# K7410tFFG900MGT.net
KiCad netlist of a schematic drawn in Altium Designer
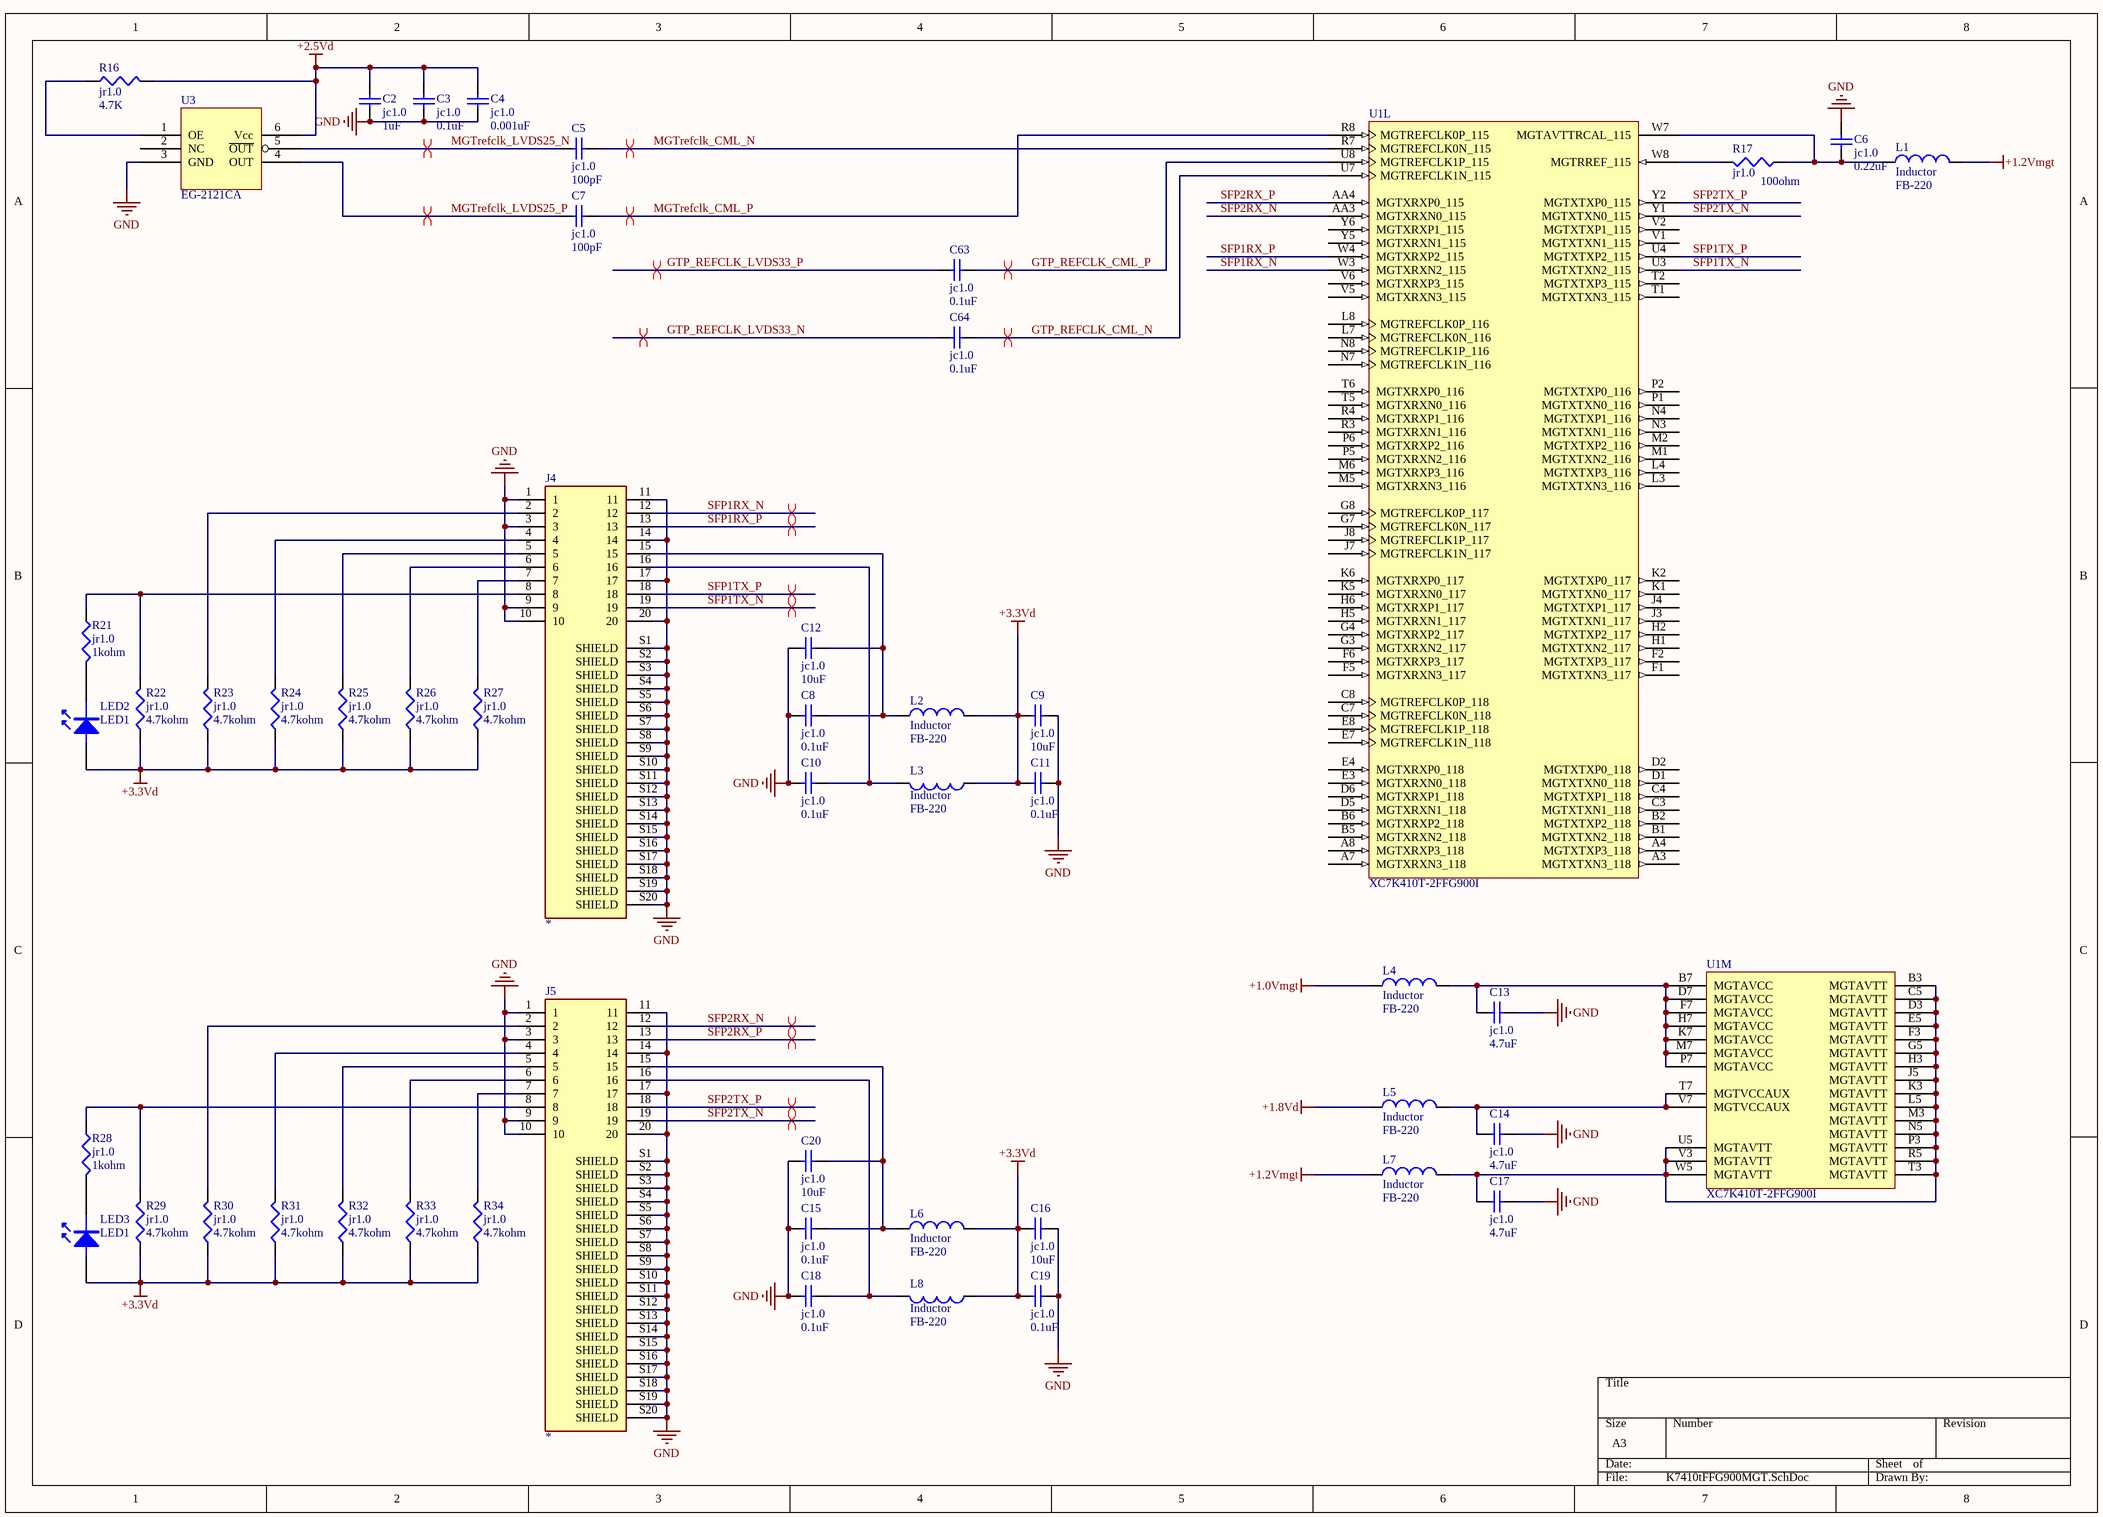
[diagram p0: K7410tFFG900MGT.SchDoc]

(export (version "E")
  (design (tool "Eeschema 10.0.6"))
  (components
    (comp (ref "C2")
      (value "jc1.0")
      (footprint "0402")
      (description "Capacitor")
      (fields (field (name "ALTIUM_VALUE") "1uF") (field (name "PUBLISHER") "Altium Limited"))
      (libsource (lib "LIB01DXP2006SchLib") (part "Cap"))
    )
    (comp (ref "C3")
      (value "jc1.0")
      (footprint "0402")
      (description "Capacitor")
      (fields (field (name "ALTIUM_VALUE") "0.1uF") (field (name "PUBLISHER") "Altium Limited"))
      (libsource (lib "LIB01DXP2006SchLib") (part "Cap"))
    )
    (comp (ref "C4")
      (value "jc1.0")
      (footprint "0402")
      (description "Capacitor")
      (fields (field (name "ALTIUM_VALUE") "0.001uF") (field (name "PUBLISHER") "Altium Limited"))
      (libsource (lib "LIB01DXP2006SchLib") (part "Cap"))
    )
    (comp (ref "C5")
      (value "jc1.0")
      (footprint "0402")
      (description "Capacitor")
      (fields (field (name "ALTIUM_VALUE") "100pF") (field (name "PUBLISHER") "Altium Limited"))
      (libsource (lib "LIB01DXP2006SchLib") (part "Cap"))
    )
    (comp (ref "C6")
      (value "jc1.0")
      (footprint "0402")
      (description "Capacitor")
      (fields (field (name "ALTIUM_VALUE") "0.22uF") (field (name "PUBLISHER") "Altium Limited"))
      (libsource (lib "LIB01DXP2006SchLib") (part "Cap"))
    )
    (comp (ref "C7")
      (value "jc1.0")
      (footprint "0402")
      (description "Capacitor")
      (fields (field (name "ALTIUM_VALUE") "100pF") (field (name "PUBLISHER") "Altium Limited"))
      (libsource (lib "LIB01DXP2006SchLib") (part "Cap"))
    )
    (comp (ref "C8")
      (value "jc1.0")
      (footprint "0805")
      (description "Capacitor")
      (fields (field (name "ALTIUM_VALUE") "0.1uF") (field (name "PUBLISHER") "Altium Limited"))
      (libsource (lib "LIB01DXP2006SchLib") (part "Cap"))
    )
    (comp (ref "C9")
      (value "jc1.0")
      (footprint "0805")
      (description "Capacitor")
      (fields (field (name "ALTIUM_VALUE") "10uF") (field (name "PUBLISHER") "Altium Limited"))
      (libsource (lib "LIB01DXP2006SchLib") (part "Cap"))
    )
    (comp (ref "C10")
      (value "jc1.0")
      (footprint "0805")
      (description "Capacitor")
      (fields (field (name "ALTIUM_VALUE") "0.1uF") (field (name "PUBLISHER") "Altium Limited"))
      (libsource (lib "LIB01DXP2006SchLib") (part "Cap"))
    )
    (comp (ref "C11")
      (value "jc1.0")
      (footprint "0805")
      (description "Capacitor")
      (fields (field (name "ALTIUM_VALUE") "0.1uF") (field (name "PUBLISHER") "Altium Limited"))
      (libsource (lib "LIB01DXP2006SchLib") (part "Cap"))
    )
    (comp (ref "C12")
      (value "jc1.0")
      (footprint "0805")
      (description "Capacitor")
      (fields (field (name "ALTIUM_VALUE") "10uF") (field (name "PUBLISHER") "Altium Limited"))
      (libsource (lib "LIB01DXP2006SchLib") (part "Cap"))
    )
    (comp (ref "C13")
      (value "jc1.0")
      (footprint "0402")
      (description "Capacitor")
      (fields (field (name "ALTIUM_VALUE") "4.7uF") (field (name "PUBLISHER") "Altium Limited"))
      (libsource (lib "LIB01DXP2006SchLib") (part "Cap"))
    )
    (comp (ref "C14")
      (value "jc1.0")
      (footprint "0402")
      (description "Capacitor")
      (fields (field (name "ALTIUM_VALUE") "4.7uF") (field (name "PUBLISHER") "Altium Limited"))
      (libsource (lib "LIB01DXP2006SchLib") (part "Cap"))
    )
    (comp (ref "C15")
      (value "jc1.0")
      (footprint "0805")
      (description "Capacitor")
      (fields (field (name "ALTIUM_VALUE") "0.1uF") (field (name "PUBLISHER") "Altium Limited"))
      (libsource (lib "LIB01DXP2006SchLib") (part "Cap"))
    )
    (comp (ref "C16")
      (value "jc1.0")
      (footprint "0805")
      (description "Capacitor")
      (fields (field (name "ALTIUM_VALUE") "10uF") (field (name "PUBLISHER") "Altium Limited"))
      (libsource (lib "LIB01DXP2006SchLib") (part "Cap"))
    )
    (comp (ref "C17")
      (value "jc1.0")
      (footprint "0402")
      (description "Capacitor")
      (fields (field (name "ALTIUM_VALUE") "4.7uF") (field (name "PUBLISHER") "Altium Limited"))
      (libsource (lib "LIB01DXP2006SchLib") (part "Cap"))
    )
    (comp (ref "C18")
      (value "jc1.0")
      (footprint "0805")
      (description "Capacitor")
      (fields (field (name "ALTIUM_VALUE") "0.1uF") (field (name "PUBLISHER") "Altium Limited"))
      (libsource (lib "LIB01DXP2006SchLib") (part "Cap"))
    )
    (comp (ref "C19")
      (value "jc1.0")
      (footprint "0805")
      (description "Capacitor")
      (fields (field (name "ALTIUM_VALUE") "0.1uF") (field (name "PUBLISHER") "Altium Limited"))
      (libsource (lib "LIB01DXP2006SchLib") (part "Cap"))
    )
    (comp (ref "C20")
      (value "jc1.0")
      (footprint "0805")
      (description "Capacitor")
      (fields (field (name "ALTIUM_VALUE") "10uF") (field (name "PUBLISHER") "Altium Limited"))
      (libsource (lib "LIB01DXP2006SchLib") (part "Cap"))
    )
    (comp (ref "C63")
      (value "jc1.0")
      (footprint "0402")
      (description "Capacitor")
      (fields (field (name "ALTIUM_VALUE") "0.1uF") (field (name "PUBLISHER") "Altium Limited"))
      (libsource (lib "LIB01DXP2006SchLib") (part "Cap"))
    )
    (comp (ref "C64")
      (value "jc1.0")
      (footprint "0402")
      (description "Capacitor")
      (fields (field (name "ALTIUM_VALUE") "0.1uF") (field (name "PUBLISHER") "Altium Limited"))
      (libsource (lib "LIB01DXP2006SchLib") (part "Cap"))
    )
    (comp (ref "J4")
      (value "2227023-1")
      (footprint "TE_2227023-1")
      (description "Connector Accessories 1 Port SFP Cage Press Fit Right Angle Through Hole Nickel Tray")
      (fields (field (name "MF") "TE Connectivity") (field (name "COMMENT_1") "*"))
      (libsource (lib "2227023-1") (part "2227023-1"))
    )
    (comp (ref "J5")
      (value "2227023-1")
      (footprint "TE_2227023-1")
      (description "Connector Accessories 1 Port SFP Cage Press Fit Right Angle Through Hole Nickel Tray")
      (fields (field (name "MF") "TE Connectivity") (field (name "COMMENT_1") "*"))
      (libsource (lib "2227023-1") (part "2227023-1"))
    )
    (comp (ref "L1")
      (value "Inductor")
      (footprint "0603")
      (fields (field (name "ALTIUM_VALUE") "FB-220") (field (name "PUBLISHER") "Altium Limited"))
      (libsource (lib "LIB01DXP2006SchLib") (part "Inductor"))
    )
    (comp (ref "L2")
      (value "Inductor")
      (footprint "1210")
      (fields (field (name "ALTIUM_VALUE") "FB-220") (field (name "PUBLISHER") "Altium Limited"))
      (libsource (lib "LIB01DXP2006SchLib") (part "Inductor"))
    )
    (comp (ref "L3")
      (value "Inductor")
      (footprint "1210")
      (fields (field (name "ALTIUM_VALUE") "FB-220") (field (name "PUBLISHER") "Altium Limited"))
      (libsource (lib "LIB01DXP2006SchLib") (part "Inductor"))
    )
    (comp (ref "L4")
      (value "Inductor")
      (footprint "1210")
      (fields (field (name "ALTIUM_VALUE") "FB-220") (field (name "PUBLISHER") "Altium Limited"))
      (libsource (lib "LIB01DXP2006SchLib") (part "Inductor"))
    )
    (comp (ref "L5")
      (value "Inductor")
      (footprint "1210")
      (fields (field (name "ALTIUM_VALUE") "FB-220") (field (name "PUBLISHER") "Altium Limited"))
      (libsource (lib "LIB01DXP2006SchLib") (part "Inductor"))
    )
    (comp (ref "L6")
      (value "Inductor")
      (footprint "1210")
      (fields (field (name "ALTIUM_VALUE") "FB-220") (field (name "PUBLISHER") "Altium Limited"))
      (libsource (lib "LIB01DXP2006SchLib") (part "Inductor"))
    )
    (comp (ref "L7")
      (value "Inductor")
      (footprint "1210")
      (fields (field (name "ALTIUM_VALUE") "FB-220") (field (name "PUBLISHER") "Altium Limited"))
      (libsource (lib "LIB01DXP2006SchLib") (part "Inductor"))
    )
    (comp (ref "L8")
      (value "Inductor")
      (footprint "1210")
      (fields (field (name "ALTIUM_VALUE") "FB-220") (field (name "PUBLISHER") "Altium Limited"))
      (libsource (lib "LIB01DXP2006SchLib") (part "Inductor"))
    )
    (comp (ref "LED2") (value "LED1") (footprint "LED1") (libsource (lib "LIB01DXP2006SchLib") (part "LED1")))
    (comp (ref "LED3") (value "LED1") (footprint "LED1") (libsource (lib "LIB01DXP2006SchLib") (part "LED1")))
    (comp (ref "R16")
      (value "jr1.0")
      (footprint "0402")
      (description "Resistor")
      (fields (field (name "ALTIUM_VALUE") "4.7K") (field (name "PUBLISHER") "Altium Limited"))
      (libsource (lib "LIB01DXP2006SchLib") (part "Res"))
    )
    (comp (ref "R17")
      (value "jr1.0")
      (footprint "0402")
      (description "Resistor")
      (fields (field (name "ALTIUM_VALUE") "100ohm") (field (name "PUBLISHER") "Altium Limited"))
      (libsource (lib "LIB01DXP2006SchLib") (part "Res"))
    )
    (comp (ref "R21")
      (value "jr1.0")
      (footprint "0402")
      (description "Resistor")
      (fields (field (name "ALTIUM_VALUE") "1kohm") (field (name "PUBLISHER") "Altium Limited"))
      (libsource (lib "LIB01DXP2006SchLib") (part "Res"))
    )
    (comp (ref "R22")
      (value "jr1.0")
      (footprint "0402")
      (description "Resistor")
      (fields (field (name "ALTIUM_VALUE") "4.7kohm") (field (name "PUBLISHER") "Altium Limited"))
      (libsource (lib "LIB01DXP2006SchLib") (part "Res"))
    )
    (comp (ref "R23")
      (value "jr1.0")
      (footprint "0402")
      (description "Resistor")
      (fields (field (name "ALTIUM_VALUE") "4.7kohm") (field (name "PUBLISHER") "Altium Limited"))
      (libsource (lib "LIB01DXP2006SchLib") (part "Res"))
    )
    (comp (ref "R24")
      (value "jr1.0")
      (footprint "0402")
      (description "Resistor")
      (fields (field (name "ALTIUM_VALUE") "4.7kohm") (field (name "PUBLISHER") "Altium Limited"))
      (libsource (lib "LIB01DXP2006SchLib") (part "Res"))
    )
    (comp (ref "R25")
      (value "jr1.0")
      (footprint "0402")
      (description "Resistor")
      (fields (field (name "ALTIUM_VALUE") "4.7kohm") (field (name "PUBLISHER") "Altium Limited"))
      (libsource (lib "LIB01DXP2006SchLib") (part "Res"))
    )
    (comp (ref "R26")
      (value "jr1.0")
      (footprint "0402")
      (description "Resistor")
      (fields (field (name "ALTIUM_VALUE") "4.7kohm") (field (name "PUBLISHER") "Altium Limited"))
      (libsource (lib "LIB01DXP2006SchLib") (part "Res"))
    )
    (comp (ref "R27")
      (value "jr1.0")
      (footprint "0402")
      (description "Resistor")
      (fields (field (name "ALTIUM_VALUE") "4.7kohm") (field (name "PUBLISHER") "Altium Limited"))
      (libsource (lib "LIB01DXP2006SchLib") (part "Res"))
    )
    (comp (ref "R28")
      (value "jr1.0")
      (footprint "0402")
      (description "Resistor")
      (fields (field (name "ALTIUM_VALUE") "1kohm") (field (name "PUBLISHER") "Altium Limited"))
      (libsource (lib "LIB01DXP2006SchLib") (part "Res"))
    )
    (comp (ref "R29")
      (value "jr1.0")
      (footprint "0402")
      (description "Resistor")
      (fields (field (name "ALTIUM_VALUE") "4.7kohm") (field (name "PUBLISHER") "Altium Limited"))
      (libsource (lib "LIB01DXP2006SchLib") (part "Res"))
    )
    (comp (ref "R30")
      (value "jr1.0")
      (footprint "0402")
      (description "Resistor")
      (fields (field (name "ALTIUM_VALUE") "4.7kohm") (field (name "PUBLISHER") "Altium Limited"))
      (libsource (lib "LIB01DXP2006SchLib") (part "Res"))
    )
    (comp (ref "R31")
      (value "jr1.0")
      (footprint "0402")
      (description "Resistor")
      (fields (field (name "ALTIUM_VALUE") "4.7kohm") (field (name "PUBLISHER") "Altium Limited"))
      (libsource (lib "LIB01DXP2006SchLib") (part "Res"))
    )
    (comp (ref "R32")
      (value "jr1.0")
      (footprint "0402")
      (description "Resistor")
      (fields (field (name "ALTIUM_VALUE") "4.7kohm") (field (name "PUBLISHER") "Altium Limited"))
      (libsource (lib "LIB01DXP2006SchLib") (part "Res"))
    )
    (comp (ref "R33")
      (value "jr1.0")
      (footprint "0402")
      (description "Resistor")
      (fields (field (name "ALTIUM_VALUE") "4.7kohm") (field (name "PUBLISHER") "Altium Limited"))
      (libsource (lib "LIB01DXP2006SchLib") (part "Res"))
    )
    (comp (ref "R34")
      (value "jr1.0")
      (footprint "0402")
      (description "Resistor")
      (fields (field (name "ALTIUM_VALUE") "4.7kohm") (field (name "PUBLISHER") "Altium Limited"))
      (libsource (lib "LIB01DXP2006SchLib") (part "Res"))
    )
    (comp (ref "U1")
      (value "XC7K410T-2FFG900I")
      (footprint "FFG900")
      (description "Kintex-7 FPGA, 500 User I/Os, 16 GTX, 900-Ball BGA, Speed Grade 2, Industrial Grade, Pb-Free")
      (fields (field (name "GENERIC PART NUMBER") "XC7K410T") (field (name "MANUFACTURER") "Xilinx"))
      (libsource (lib "Xilinx Kintex-7") (part "XC7K410T-2FFG900I"))
    )
    (comp (ref "U3")
      (value "EG-2121CA")
      (footprint "DFN3")
      (libsource (lib "LIB01DXP2006SchLib") (part "EG-2121CA"))
    )
  )
  (nets
    (net (code "1") (name "+1.0Vmgt") (class "Default")
      (node (ref "L4") (pin "1") (pinfunction "1_1") (pintype "passive"))
    )
    (net (code "2") (name "+1.2Vmgt") (class "Default")
      (node (ref "L1") (pin "2") (pinfunction "2_2") (pintype "passive"))
      (node (ref "L7") (pin "1") (pinfunction "1_1") (pintype "passive"))
    )
    (net (code "3") (name "+1.8Vd") (class "Default")
      (node (ref "L5") (pin "1") (pinfunction "1_1") (pintype "passive"))
    )
    (net (code "4") (name "+2.5Vd") (class "Default")
      (node (ref "C2") (pin "2") (pinfunction "2_2") (pintype "passive"))
      (node (ref "C3") (pin "2") (pinfunction "2_2") (pintype "passive"))
      (node (ref "C4") (pin "2") (pinfunction "2_2") (pintype "passive"))
      (node (ref "R16") (pin "2") (pinfunction "2_2") (pintype "passive"))
      (node (ref "U3") (pin "6") (pinfunction "Vcc_6") (pintype "passive"))
    )
    (net (code "5") (name "+3.3Vd") (class "Default")
      (node (ref "C11") (pin "2") (pinfunction "2_2") (pintype "passive"))
      (node (ref "C16") (pin "2") (pinfunction "2_2") (pintype "passive"))
      (node (ref "C19") (pin "2") (pinfunction "2_2") (pintype "passive"))
      (node (ref "C9") (pin "2") (pinfunction "2_2") (pintype "passive"))
      (node (ref "L2") (pin "2") (pinfunction "2_2") (pintype "passive"))
      (node (ref "L3") (pin "1") (pinfunction "1_1") (pintype "passive"))
      (node (ref "L6") (pin "2") (pinfunction "2_2") (pintype "passive"))
      (node (ref "L8") (pin "1") (pinfunction "1_1") (pintype "passive"))
      (node (ref "LED2") (pin "1") (pinfunction "1_1") (pintype "passive"))
      (node (ref "LED3") (pin "1") (pinfunction "1_1") (pintype "passive"))
      (node (ref "R22") (pin "1") (pinfunction "1_1") (pintype "passive"))
      (node (ref "R23") (pin "1") (pinfunction "1_1") (pintype "passive"))
      (node (ref "R24") (pin "1") (pinfunction "1_1") (pintype "passive"))
      (node (ref "R25") (pin "1") (pinfunction "1_1") (pintype "passive"))
      (node (ref "R26") (pin "1") (pinfunction "1_1") (pintype "passive"))
      (node (ref "R27") (pin "1") (pinfunction "1_1") (pintype "passive"))
      (node (ref "R29") (pin "1") (pinfunction "1_1") (pintype "passive"))
      (node (ref "R30") (pin "1") (pinfunction "1_1") (pintype "passive"))
      (node (ref "R31") (pin "1") (pinfunction "1_1") (pintype "passive"))
      (node (ref "R32") (pin "1") (pinfunction "1_1") (pintype "passive"))
      (node (ref "R33") (pin "1") (pinfunction "1_1") (pintype "passive"))
      (node (ref "R34") (pin "1") (pinfunction "1_1") (pintype "passive"))
    )
    (net (code "6") (name "/GTP_REFCLK_CML_N") (class "Default")
      (node (ref "C64") (pin "2") (pinfunction "2_2") (pintype "passive"))
      (node (ref "U1") (pin "U7") (pinfunction "MGTREFCLK1N_115_U7") (pintype "input"))
    )
    (net (code "7") (name "/GTP_REFCLK_CML_P") (class "Default")
      (node (ref "C63") (pin "2") (pinfunction "2_2") (pintype "passive"))
      (node (ref "U1") (pin "U8") (pinfunction "MGTREFCLK1P_115_U8") (pintype "input"))
    )
    (net (code "8") (name "/GTP_REFCLK_LVDS33_N") (class "Default")
      (node (ref "C64") (pin "1") (pinfunction "1_1") (pintype "passive"))
    )
    (net (code "9") (name "/GTP_REFCLK_LVDS33_P") (class "Default")
      (node (ref "C63") (pin "1") (pinfunction "1_1") (pintype "passive"))
    )
    (net (code "10") (name "/MGTrefclk_CML_N") (class "Default")
      (node (ref "C5") (pin "2") (pinfunction "2_2") (pintype "passive"))
      (node (ref "U1") (pin "R7") (pinfunction "MGTREFCLK0N_115_R7") (pintype "input"))
    )
    (net (code "11") (name "/MGTrefclk_CML_P") (class "Default")
      (node (ref "C7") (pin "2") (pinfunction "2_2") (pintype "passive"))
      (node (ref "U1") (pin "R8") (pinfunction "MGTREFCLK0P_115_R8") (pintype "input"))
    )
    (net (code "12") (name "/MGTrefclk_LVDS25_N") (class "Default")
      (node (ref "C5") (pin "1") (pinfunction "1_1") (pintype "passive"))
      (node (ref "U3") (pin "5") (pinfunction "~{OUT}_5") (pintype "passive"))
    )
    (net (code "13") (name "/MGTrefclk_LVDS25_P") (class "Default")
      (node (ref "C7") (pin "1") (pinfunction "1_1") (pintype "passive"))
      (node (ref "U3") (pin "4") (pinfunction "OUT_4") (pintype "passive"))
    )
    (net (code "14") (name "/SFP1RX_N") (class "Default")
      (node (ref "J4") (pin "12") (pinfunction "12_12") (pintype "passive"))
      (node (ref "U1") (pin "W3") (pinfunction "MGTXRXN2_115_W3") (pintype "input"))
    )
    (net (code "15") (name "/SFP1RX_P") (class "Default")
      (node (ref "J4") (pin "13") (pinfunction "13_13") (pintype "passive"))
      (node (ref "U1") (pin "W4") (pinfunction "MGTXRXP2_115_W4") (pintype "input"))
    )
    (net (code "16") (name "/SFP1TX_N") (class "Default")
      (node (ref "J4") (pin "19") (pinfunction "19_19") (pintype "passive"))
      (node (ref "U1") (pin "U3") (pinfunction "MGTXTXN2_115_U3") (pintype "output"))
    )
    (net (code "17") (name "/SFP1TX_P") (class "Default")
      (node (ref "J4") (pin "18") (pinfunction "18_18") (pintype "passive"))
      (node (ref "U1") (pin "U4") (pinfunction "MGTXTXP2_115_U4") (pintype "output"))
    )
    (net (code "18") (name "/SFP2RX_N") (class "Default")
      (node (ref "J5") (pin "12") (pinfunction "12_12") (pintype "passive"))
      (node (ref "U1") (pin "AA3") (pinfunction "MGTXRXN0_115_AA3") (pintype "input"))
    )
    (net (code "19") (name "/SFP2RX_P") (class "Default")
      (node (ref "J5") (pin "13") (pinfunction "13_13") (pintype "passive"))
      (node (ref "U1") (pin "AA4") (pinfunction "MGTXRXP0_115_AA4") (pintype "input"))
    )
    (net (code "20") (name "/SFP2TX_N") (class "Default")
      (node (ref "J5") (pin "19") (pinfunction "19_19") (pintype "passive"))
      (node (ref "U1") (pin "Y1") (pinfunction "MGTXTXN0_115_Y1") (pintype "output"))
    )
    (net (code "21") (name "/SFP2TX_P") (class "Default")
      (node (ref "J5") (pin "18") (pinfunction "18_18") (pintype "passive"))
      (node (ref "U1") (pin "Y2") (pinfunction "MGTXTXP0_115_Y2") (pintype "output"))
    )
    (net (code "22") (name "GND") (class "Default")
      (node (ref "C10") (pin "1") (pinfunction "1_1") (pintype "passive"))
      (node (ref "C11") (pin "1") (pinfunction "1_1") (pintype "passive"))
      (node (ref "C12") (pin "1") (pinfunction "1_1") (pintype "passive"))
      (node (ref "C13") (pin "1") (pinfunction "1_1") (pintype "passive"))
      (node (ref "C14") (pin "1") (pinfunction "1_1") (pintype "passive"))
      (node (ref "C15") (pin "1") (pinfunction "1_1") (pintype "passive"))
      (node (ref "C16") (pin "1") (pinfunction "1_1") (pintype "passive"))
      (node (ref "C17") (pin "1") (pinfunction "1_1") (pintype "passive"))
      (node (ref "C18") (pin "1") (pinfunction "1_1") (pintype "passive"))
      (node (ref "C19") (pin "1") (pinfunction "1_1") (pintype "passive"))
      (node (ref "C2") (pin "1") (pinfunction "1_1") (pintype "passive"))
      (node (ref "C20") (pin "1") (pinfunction "1_1") (pintype "passive"))
      (node (ref "C3") (pin "1") (pinfunction "1_1") (pintype "passive"))
      (node (ref "C4") (pin "1") (pinfunction "1_1") (pintype "passive"))
      (node (ref "C6") (pin "1") (pinfunction "1_1") (pintype "passive"))
      (node (ref "C8") (pin "1") (pinfunction "1_1") (pintype "passive"))
      (node (ref "C9") (pin "1") (pinfunction "1_1") (pintype "passive"))
      (node (ref "J4") (pin "1") (pinfunction "1_1") (pintype "passive"))
      (node (ref "J4") (pin "10") (pinfunction "10_10") (pintype "passive"))
      (node (ref "J4") (pin "11") (pinfunction "11_11") (pintype "passive"))
      (node (ref "J4") (pin "14") (pinfunction "14_14") (pintype "passive"))
      (node (ref "J4") (pin "17") (pinfunction "17_17") (pintype "passive"))
      (node (ref "J4") (pin "20") (pinfunction "20_20") (pintype "passive"))
      (node (ref "J4") (pin "3") (pinfunction "3_3") (pintype "passive"))
      (node (ref "J4") (pin "9") (pinfunction "9_9") (pintype "passive"))
      (node (ref "J4") (pin "S1") (pinfunction "SHIELD_S1") (pintype "passive"))
      (node (ref "J4") (pin "S10") (pinfunction "SHIELD_S10") (pintype "passive"))
      (node (ref "J4") (pin "S11") (pinfunction "SHIELD_S11") (pintype "passive"))
      (node (ref "J4") (pin "S12") (pinfunction "SHIELD_S12") (pintype "passive"))
      (node (ref "J4") (pin "S13") (pinfunction "SHIELD_S13") (pintype "passive"))
      (node (ref "J4") (pin "S14") (pinfunction "SHIELD_S14") (pintype "passive"))
      (node (ref "J4") (pin "S15") (pinfunction "SHIELD_S15") (pintype "passive"))
      (node (ref "J4") (pin "S16") (pinfunction "SHIELD_S16") (pintype "passive"))
      (node (ref "J4") (pin "S17") (pinfunction "SHIELD_S17") (pintype "passive"))
      (node (ref "J4") (pin "S18") (pinfunction "SHIELD_S18") (pintype "passive"))
      (node (ref "J4") (pin "S19") (pinfunction "SHIELD_S19") (pintype "passive"))
      (node (ref "J4") (pin "S2") (pinfunction "SHIELD_S2") (pintype "passive"))
      (node (ref "J4") (pin "S20") (pinfunction "SHIELD_S20") (pintype "passive"))
      (node (ref "J4") (pin "S3") (pinfunction "SHIELD_S3") (pintype "passive"))
      (node (ref "J4") (pin "S4") (pinfunction "SHIELD_S4") (pintype "passive"))
      (node (ref "J4") (pin "S5") (pinfunction "SHIELD_S5") (pintype "passive"))
      (node (ref "J4") (pin "S6") (pinfunction "SHIELD_S6") (pintype "passive"))
      (node (ref "J4") (pin "S7") (pinfunction "SHIELD_S7") (pintype "passive"))
      (node (ref "J4") (pin "S8") (pinfunction "SHIELD_S8") (pintype "passive"))
      (node (ref "J4") (pin "S9") (pinfunction "SHIELD_S9") (pintype "passive"))
      (node (ref "J5") (pin "1") (pinfunction "1_1") (pintype "passive"))
      (node (ref "J5") (pin "10") (pinfunction "10_10") (pintype "passive"))
      (node (ref "J5") (pin "11") (pinfunction "11_11") (pintype "passive"))
      (node (ref "J5") (pin "14") (pinfunction "14_14") (pintype "passive"))
      (node (ref "J5") (pin "17") (pinfunction "17_17") (pintype "passive"))
      (node (ref "J5") (pin "20") (pinfunction "20_20") (pintype "passive"))
      (node (ref "J5") (pin "3") (pinfunction "3_3") (pintype "passive"))
      (node (ref "J5") (pin "9") (pinfunction "9_9") (pintype "passive"))
      (node (ref "J5") (pin "S1") (pinfunction "SHIELD_S1") (pintype "passive"))
      (node (ref "J5") (pin "S10") (pinfunction "SHIELD_S10") (pintype "passive"))
      (node (ref "J5") (pin "S11") (pinfunction "SHIELD_S11") (pintype "passive"))
      (node (ref "J5") (pin "S12") (pinfunction "SHIELD_S12") (pintype "passive"))
      (node (ref "J5") (pin "S13") (pinfunction "SHIELD_S13") (pintype "passive"))
      (node (ref "J5") (pin "S14") (pinfunction "SHIELD_S14") (pintype "passive"))
      (node (ref "J5") (pin "S15") (pinfunction "SHIELD_S15") (pintype "passive"))
      (node (ref "J5") (pin "S16") (pinfunction "SHIELD_S16") (pintype "passive"))
      (node (ref "J5") (pin "S17") (pinfunction "SHIELD_S17") (pintype "passive"))
      (node (ref "J5") (pin "S18") (pinfunction "SHIELD_S18") (pintype "passive"))
      (node (ref "J5") (pin "S19") (pinfunction "SHIELD_S19") (pintype "passive"))
      (node (ref "J5") (pin "S2") (pinfunction "SHIELD_S2") (pintype "passive"))
      (node (ref "J5") (pin "S20") (pinfunction "SHIELD_S20") (pintype "passive"))
      (node (ref "J5") (pin "S3") (pinfunction "SHIELD_S3") (pintype "passive"))
      (node (ref "J5") (pin "S4") (pinfunction "SHIELD_S4") (pintype "passive"))
      (node (ref "J5") (pin "S5") (pinfunction "SHIELD_S5") (pintype "passive"))
      (node (ref "J5") (pin "S6") (pinfunction "SHIELD_S6") (pintype "passive"))
      (node (ref "J5") (pin "S7") (pinfunction "SHIELD_S7") (pintype "passive"))
      (node (ref "J5") (pin "S8") (pinfunction "SHIELD_S8") (pintype "passive"))
      (node (ref "J5") (pin "S9") (pinfunction "SHIELD_S9") (pintype "passive"))
      (node (ref "U3") (pin "3") (pinfunction "GND_3") (pintype "passive"))
    )
    (net (code "23") (name "Net-(C10-Pad2)") (class "Default")
      (node (ref "C10") (pin "2") (pinfunction "2_2") (pintype "passive"))
      (node (ref "J4") (pin "16") (pinfunction "16_16") (pintype "passive"))
      (node (ref "L3") (pin "2") (pinfunction "2_2") (pintype "passive"))
    )
    (net (code "24") (name "Net-(C12-Pad2)") (class "Default")
      (node (ref "C12") (pin "2") (pinfunction "2_2") (pintype "passive"))
      (node (ref "C8") (pin "2") (pinfunction "2_2") (pintype "passive"))
      (node (ref "J4") (pin "15") (pinfunction "15_15") (pintype "passive"))
      (node (ref "L2") (pin "1") (pinfunction "1_1") (pintype "passive"))
    )
    (net (code "25") (name "Net-(C13-Pad2)") (class "Default")
      (node (ref "C13") (pin "2") (pinfunction "2_2") (pintype "passive"))
      (node (ref "L4") (pin "2") (pinfunction "2_2") (pintype "passive"))
      (node (ref "U1") (pin "B7") (pinfunction "MGTAVCC_B7") (pintype "power_in"))
      (node (ref "U1") (pin "D7") (pinfunction "MGTAVCC_D7") (pintype "power_in"))
      (node (ref "U1") (pin "F7") (pinfunction "MGTAVCC_F7") (pintype "power_in"))
      (node (ref "U1") (pin "H7") (pinfunction "MGTAVCC_H7") (pintype "power_in"))
      (node (ref "U1") (pin "K7") (pinfunction "MGTAVCC_K7") (pintype "power_in"))
      (node (ref "U1") (pin "M7") (pinfunction "MGTAVCC_M7") (pintype "power_in"))
      (node (ref "U1") (pin "P7") (pinfunction "MGTAVCC_P7") (pintype "power_in"))
    )
    (net (code "26") (name "Net-(C14-Pad2)") (class "Default")
      (node (ref "C14") (pin "2") (pinfunction "2_2") (pintype "passive"))
      (node (ref "L5") (pin "2") (pinfunction "2_2") (pintype "passive"))
      (node (ref "U1") (pin "T7") (pinfunction "MGTVCCAUX_T7") (pintype "power_in"))
      (node (ref "U1") (pin "V7") (pinfunction "MGTVCCAUX_V7") (pintype "power_in"))
    )
    (net (code "27") (name "Net-(C15-Pad2)") (class "Default")
      (node (ref "C15") (pin "2") (pinfunction "2_2") (pintype "passive"))
      (node (ref "C20") (pin "2") (pinfunction "2_2") (pintype "passive"))
      (node (ref "J5") (pin "15") (pinfunction "15_15") (pintype "passive"))
      (node (ref "L6") (pin "1") (pinfunction "1_1") (pintype "passive"))
    )
    (net (code "28") (name "Net-(C17-Pad2)") (class "Default")
      (node (ref "C17") (pin "2") (pinfunction "2_2") (pintype "passive"))
      (node (ref "L7") (pin "2") (pinfunction "2_2") (pintype "passive"))
      (node (ref "U1") (pin "B3") (pinfunction "MGTAVTT_B3") (pintype "power_in"))
      (node (ref "U1") (pin "C5") (pinfunction "MGTAVTT_C5") (pintype "power_in"))
      (node (ref "U1") (pin "D3") (pinfunction "MGTAVTT_D3") (pintype "power_in"))
      (node (ref "U1") (pin "E5") (pinfunction "MGTAVTT_E5") (pintype "power_in"))
      (node (ref "U1") (pin "F3") (pinfunction "MGTAVTT_F3") (pintype "power_in"))
      (node (ref "U1") (pin "G5") (pinfunction "MGTAVTT_G5") (pintype "power_in"))
      (node (ref "U1") (pin "H3") (pinfunction "MGTAVTT_H3") (pintype "power_in"))
      (node (ref "U1") (pin "J5") (pinfunction "MGTAVTT_J5") (pintype "power_in"))
      (node (ref "U1") (pin "K3") (pinfunction "MGTAVTT_K3") (pintype "power_in"))
      (node (ref "U1") (pin "L5") (pinfunction "MGTAVTT_L5") (pintype "power_in"))
      (node (ref "U1") (pin "M3") (pinfunction "MGTAVTT_M3") (pintype "power_in"))
      (node (ref "U1") (pin "N5") (pinfunction "MGTAVTT_N5") (pintype "power_in"))
      (node (ref "U1") (pin "P3") (pinfunction "MGTAVTT_P3") (pintype "power_in"))
      (node (ref "U1") (pin "R5") (pinfunction "MGTAVTT_R5") (pintype "power_in"))
      (node (ref "U1") (pin "T3") (pinfunction "MGTAVTT_T3") (pintype "power_in"))
      (node (ref "U1") (pin "U5") (pinfunction "MGTAVTT_U5") (pintype "power_in"))
      (node (ref "U1") (pin "V3") (pinfunction "MGTAVTT_V3") (pintype "power_in"))
      (node (ref "U1") (pin "W5") (pinfunction "MGTAVTT_W5") (pintype "power_in"))
    )
    (net (code "29") (name "Net-(C18-Pad2)") (class "Default")
      (node (ref "C18") (pin "2") (pinfunction "2_2") (pintype "passive"))
      (node (ref "J5") (pin "16") (pinfunction "16_16") (pintype "passive"))
      (node (ref "L8") (pin "2") (pinfunction "2_2") (pintype "passive"))
    )
    (net (code "30") (name "Net-(J4-Pad2)") (class "Default")
      (node (ref "J4") (pin "2") (pinfunction "2_2") (pintype "passive"))
      (node (ref "R23") (pin "2") (pinfunction "2_2") (pintype "passive"))
    )
    (net (code "31") (name "Net-(J4-Pad4)") (class "Default")
      (node (ref "J4") (pin "4") (pinfunction "4_4") (pintype "passive"))
      (node (ref "R24") (pin "2") (pinfunction "2_2") (pintype "passive"))
    )
    (net (code "32") (name "Net-(J4-Pad5)") (class "Default")
      (node (ref "J4") (pin "5") (pinfunction "5_5") (pintype "passive"))
      (node (ref "R25") (pin "2") (pinfunction "2_2") (pintype "passive"))
    )
    (net (code "33") (name "Net-(J4-Pad6)") (class "Default")
      (node (ref "J4") (pin "6") (pinfunction "6_6") (pintype "passive"))
      (node (ref "R26") (pin "2") (pinfunction "2_2") (pintype "passive"))
    )
    (net (code "34") (name "Net-(J4-Pad7)") (class "Default")
      (node (ref "J4") (pin "7") (pinfunction "7_7") (pintype "passive"))
      (node (ref "R27") (pin "2") (pinfunction "2_2") (pintype "passive"))
    )
    (net (code "35") (name "Net-(J4-Pad8)") (class "Default")
      (node (ref "J4") (pin "8") (pinfunction "8_8") (pintype "passive"))
      (node (ref "R21") (pin "1") (pinfunction "1_1") (pintype "passive"))
      (node (ref "R22") (pin "2") (pinfunction "2_2") (pintype "passive"))
    )
    (net (code "36") (name "Net-(J5-Pad2)") (class "Default")
      (node (ref "J5") (pin "2") (pinfunction "2_2") (pintype "passive"))
      (node (ref "R30") (pin "2") (pinfunction "2_2") (pintype "passive"))
    )
    (net (code "37") (name "Net-(J5-Pad4)") (class "Default")
      (node (ref "J5") (pin "4") (pinfunction "4_4") (pintype "passive"))
      (node (ref "R31") (pin "2") (pinfunction "2_2") (pintype "passive"))
    )
    (net (code "38") (name "Net-(J5-Pad5)") (class "Default")
      (node (ref "J5") (pin "5") (pinfunction "5_5") (pintype "passive"))
      (node (ref "R32") (pin "2") (pinfunction "2_2") (pintype "passive"))
    )
    (net (code "39") (name "Net-(J5-Pad6)") (class "Default")
      (node (ref "J5") (pin "6") (pinfunction "6_6") (pintype "passive"))
      (node (ref "R33") (pin "2") (pinfunction "2_2") (pintype "passive"))
    )
    (net (code "40") (name "Net-(J5-Pad7)") (class "Default")
      (node (ref "J5") (pin "7") (pinfunction "7_7") (pintype "passive"))
      (node (ref "R34") (pin "2") (pinfunction "2_2") (pintype "passive"))
    )
    (net (code "41") (name "Net-(J5-Pad8)") (class "Default")
      (node (ref "J5") (pin "8") (pinfunction "8_8") (pintype "passive"))
      (node (ref "R28") (pin "1") (pinfunction "1_1") (pintype "passive"))
      (node (ref "R29") (pin "2") (pinfunction "2_2") (pintype "passive"))
    )
    (net (code "42") (name "Net-(LED2-Pad2)") (class "Default")
      (node (ref "LED2") (pin "2") (pinfunction "2_2") (pintype "passive"))
      (node (ref "R21") (pin "2") (pinfunction "2_2") (pintype "passive"))
    )
    (net (code "43") (name "Net-(LED3-Pad2)") (class "Default")
      (node (ref "LED3") (pin "2") (pinfunction "2_2") (pintype "passive"))
      (node (ref "R28") (pin "2") (pinfunction "2_2") (pintype "passive"))
    )
    (net (code "44") (name "Net-(U1L-MGTAVTTRCAL_115)") (class "Default")
      (node (ref "C6") (pin "2") (pinfunction "2_2") (pintype "passive"))
      (node (ref "L1") (pin "1") (pinfunction "1_1") (pintype "passive"))
      (node (ref "R17") (pin "1") (pinfunction "1_1") (pintype "passive"))
      (node (ref "U1") (pin "W7") (pinfunction "MGTAVTTRCAL_115_W7") (pintype "passive"))
    )
    (net (code "45") (name "Net-(U1L-MGTRREF_115)") (class "Default")
      (node (ref "R17") (pin "2") (pinfunction "2_2") (pintype "passive"))
      (node (ref "U1") (pin "W8") (pinfunction "MGTRREF_115_W8") (pintype "input"))
    )
    (net (code "46") (name "Net-(U3-OE)") (class "Default")
      (node (ref "R16") (pin "1") (pinfunction "1_1") (pintype "passive"))
      (node (ref "U3") (pin "1") (pinfunction "OE_1") (pintype "passive"))
    )
    (net (code "47") (name "unconnected-(U1L-MGTREFCLK0N_116-PadL7)") (class "Default")
      (node (ref "U1") (pin "L7") (pinfunction "MGTREFCLK0N_116_L7") (pintype "input"))
    )
    (net (code "48") (name "unconnected-(U1L-MGTREFCLK0N_117-PadG7)") (class "Default")
      (node (ref "U1") (pin "G7") (pinfunction "MGTREFCLK0N_117_G7") (pintype "input"))
    )
    (net (code "49") (name "unconnected-(U1L-MGTREFCLK0N_118-PadC7)") (class "Default")
      (node (ref "U1") (pin "C7") (pinfunction "MGTREFCLK0N_118_C7") (pintype "input"))
    )
    (net (code "50") (name "unconnected-(U1L-MGTREFCLK0P_116-PadL8)") (class "Default")
      (node (ref "U1") (pin "L8") (pinfunction "MGTREFCLK0P_116_L8") (pintype "input"))
    )
    (net (code "51") (name "unconnected-(U1L-MGTREFCLK0P_117-PadG8)") (class "Default")
      (node (ref "U1") (pin "G8") (pinfunction "MGTREFCLK0P_117_G8") (pintype "input"))
    )
    (net (code "52") (name "unconnected-(U1L-MGTREFCLK0P_118-PadC8)") (class "Default")
      (node (ref "U1") (pin "C8") (pinfunction "MGTREFCLK0P_118_C8") (pintype "input"))
    )
    (net (code "53") (name "unconnected-(U1L-MGTREFCLK1N_116-PadN7)") (class "Default")
      (node (ref "U1") (pin "N7") (pinfunction "MGTREFCLK1N_116_N7") (pintype "input"))
    )
    (net (code "54") (name "unconnected-(U1L-MGTREFCLK1N_117-PadJ7)") (class "Default")
      (node (ref "U1") (pin "J7") (pinfunction "MGTREFCLK1N_117_J7") (pintype "input"))
    )
    (net (code "55") (name "unconnected-(U1L-MGTREFCLK1N_118-PadE7)") (class "Default")
      (node (ref "U1") (pin "E7") (pinfunction "MGTREFCLK1N_118_E7") (pintype "input"))
    )
    (net (code "56") (name "unconnected-(U1L-MGTREFCLK1P_116-PadN8)") (class "Default")
      (node (ref "U1") (pin "N8") (pinfunction "MGTREFCLK1P_116_N8") (pintype "input"))
    )
    (net (code "57") (name "unconnected-(U1L-MGTREFCLK1P_117-PadJ8)") (class "Default")
      (node (ref "U1") (pin "J8") (pinfunction "MGTREFCLK1P_117_J8") (pintype "input"))
    )
    (net (code "58") (name "unconnected-(U1L-MGTREFCLK1P_118-PadE8)") (class "Default")
      (node (ref "U1") (pin "E8") (pinfunction "MGTREFCLK1P_118_E8") (pintype "input"))
    )
    (net (code "59") (name "unconnected-(U1L-MGTXRXN0_116-PadT5)") (class "Default")
      (node (ref "U1") (pin "T5") (pinfunction "MGTXRXN0_116_T5") (pintype "input"))
    )
    (net (code "60") (name "unconnected-(U1L-MGTXRXN0_117-PadK5)") (class "Default")
      (node (ref "U1") (pin "K5") (pinfunction "MGTXRXN0_117_K5") (pintype "input"))
    )
    (net (code "61") (name "unconnected-(U1L-MGTXRXN0_118-PadE3)") (class "Default")
      (node (ref "U1") (pin "E3") (pinfunction "MGTXRXN0_118_E3") (pintype "input"))
    )
    (net (code "62") (name "unconnected-(U1L-MGTXRXN1_115-PadY5)") (class "Default")
      (node (ref "U1") (pin "Y5") (pinfunction "MGTXRXN1_115_Y5") (pintype "input"))
    )
    (net (code "63") (name "unconnected-(U1L-MGTXRXN1_116-PadR3)") (class "Default")
      (node (ref "U1") (pin "R3") (pinfunction "MGTXRXN1_116_R3") (pintype "input"))
    )
    (net (code "64") (name "unconnected-(U1L-MGTXRXN1_117-PadH5)") (class "Default")
      (node (ref "U1") (pin "H5") (pinfunction "MGTXRXN1_117_H5") (pintype "input"))
    )
    (net (code "65") (name "unconnected-(U1L-MGTXRXN1_118-PadD5)") (class "Default")
      (node (ref "U1") (pin "D5") (pinfunction "MGTXRXN1_118_D5") (pintype "input"))
    )
    (net (code "66") (name "unconnected-(U1L-MGTXRXN2_116-PadP5)") (class "Default")
      (node (ref "U1") (pin "P5") (pinfunction "MGTXRXN2_116_P5") (pintype "input"))
    )
    (net (code "67") (name "unconnected-(U1L-MGTXRXN2_117-PadG3)") (class "Default")
      (node (ref "U1") (pin "G3") (pinfunction "MGTXRXN2_117_G3") (pintype "input"))
    )
    (net (code "68") (name "unconnected-(U1L-MGTXRXN2_118-PadB5)") (class "Default")
      (node (ref "U1") (pin "B5") (pinfunction "MGTXRXN2_118_B5") (pintype "input"))
    )
    (net (code "69") (name "unconnected-(U1L-MGTXRXN3_115-PadV5)") (class "Default")
      (node (ref "U1") (pin "V5") (pinfunction "MGTXRXN3_115_V5") (pintype "input"))
    )
    (net (code "70") (name "unconnected-(U1L-MGTXRXN3_116-PadM5)") (class "Default")
      (node (ref "U1") (pin "M5") (pinfunction "MGTXRXN3_116_M5") (pintype "input"))
    )
    (net (code "71") (name "unconnected-(U1L-MGTXRXN3_117-PadF5)") (class "Default")
      (node (ref "U1") (pin "F5") (pinfunction "MGTXRXN3_117_F5") (pintype "input"))
    )
    (net (code "72") (name "unconnected-(U1L-MGTXRXN3_118-PadA7)") (class "Default")
      (node (ref "U1") (pin "A7") (pinfunction "MGTXRXN3_118_A7") (pintype "input"))
    )
    (net (code "73") (name "unconnected-(U1L-MGTXRXP0_116-PadT6)") (class "Default")
      (node (ref "U1") (pin "T6") (pinfunction "MGTXRXP0_116_T6") (pintype "input"))
    )
    (net (code "74") (name "unconnected-(U1L-MGTXRXP0_117-PadK6)") (class "Default")
      (node (ref "U1") (pin "K6") (pinfunction "MGTXRXP0_117_K6") (pintype "input"))
    )
    (net (code "75") (name "unconnected-(U1L-MGTXRXP0_118-PadE4)") (class "Default")
      (node (ref "U1") (pin "E4") (pinfunction "MGTXRXP0_118_E4") (pintype "input"))
    )
    (net (code "76") (name "unconnected-(U1L-MGTXRXP1_115-PadY6)") (class "Default")
      (node (ref "U1") (pin "Y6") (pinfunction "MGTXRXP1_115_Y6") (pintype "input"))
    )
    (net (code "77") (name "unconnected-(U1L-MGTXRXP1_116-PadR4)") (class "Default")
      (node (ref "U1") (pin "R4") (pinfunction "MGTXRXP1_116_R4") (pintype "input"))
    )
    (net (code "78") (name "unconnected-(U1L-MGTXRXP1_117-PadH6)") (class "Default")
      (node (ref "U1") (pin "H6") (pinfunction "MGTXRXP1_117_H6") (pintype "input"))
    )
    (net (code "79") (name "unconnected-(U1L-MGTXRXP1_118-PadD6)") (class "Default")
      (node (ref "U1") (pin "D6") (pinfunction "MGTXRXP1_118_D6") (pintype "input"))
    )
    (net (code "80") (name "unconnected-(U1L-MGTXRXP2_116-PadP6)") (class "Default")
      (node (ref "U1") (pin "P6") (pinfunction "MGTXRXP2_116_P6") (pintype "input"))
    )
    (net (code "81") (name "unconnected-(U1L-MGTXRXP2_117-PadG4)") (class "Default")
      (node (ref "U1") (pin "G4") (pinfunction "MGTXRXP2_117_G4") (pintype "input"))
    )
    (net (code "82") (name "unconnected-(U1L-MGTXRXP2_118-PadB6)") (class "Default")
      (node (ref "U1") (pin "B6") (pinfunction "MGTXRXP2_118_B6") (pintype "input"))
    )
    (net (code "83") (name "unconnected-(U1L-MGTXRXP3_115-PadV6)") (class "Default")
      (node (ref "U1") (pin "V6") (pinfunction "MGTXRXP3_115_V6") (pintype "input"))
    )
    (net (code "84") (name "unconnected-(U1L-MGTXRXP3_116-PadM6)") (class "Default")
      (node (ref "U1") (pin "M6") (pinfunction "MGTXRXP3_116_M6") (pintype "input"))
    )
    (net (code "85") (name "unconnected-(U1L-MGTXRXP3_117-PadF6)") (class "Default")
      (node (ref "U1") (pin "F6") (pinfunction "MGTXRXP3_117_F6") (pintype "input"))
    )
    (net (code "86") (name "unconnected-(U1L-MGTXRXP3_118-PadA8)") (class "Default")
      (node (ref "U1") (pin "A8") (pinfunction "MGTXRXP3_118_A8") (pintype "input"))
    )
    (net (code "87") (name "unconnected-(U1L-MGTXTXN0_116-PadP1)") (class "Default")
      (node (ref "U1") (pin "P1") (pinfunction "MGTXTXN0_116_P1") (pintype "output"))
    )
    (net (code "88") (name "unconnected-(U1L-MGTXTXN0_117-PadK1)") (class "Default")
      (node (ref "U1") (pin "K1") (pinfunction "MGTXTXN0_117_K1") (pintype "output"))
    )
    (net (code "89") (name "unconnected-(U1L-MGTXTXN0_118-PadD1)") (class "Default")
      (node (ref "U1") (pin "D1") (pinfunction "MGTXTXN0_118_D1") (pintype "output"))
    )
    (net (code "90") (name "unconnected-(U1L-MGTXTXN1_115-PadV1)") (class "Default")
      (node (ref "U1") (pin "V1") (pinfunction "MGTXTXN1_115_V1") (pintype "output"))
    )
    (net (code "91") (name "unconnected-(U1L-MGTXTXN1_116-PadN3)") (class "Default")
      (node (ref "U1") (pin "N3") (pinfunction "MGTXTXN1_116_N3") (pintype "output"))
    )
    (net (code "92") (name "unconnected-(U1L-MGTXTXN1_117-PadJ3)") (class "Default")
      (node (ref "U1") (pin "J3") (pinfunction "MGTXTXN1_117_J3") (pintype "output"))
    )
    (net (code "93") (name "unconnected-(U1L-MGTXTXN1_118-PadC3)") (class "Default")
      (node (ref "U1") (pin "C3") (pinfunction "MGTXTXN1_118_C3") (pintype "output"))
    )
    (net (code "94") (name "unconnected-(U1L-MGTXTXN2_116-PadM1)") (class "Default")
      (node (ref "U1") (pin "M1") (pinfunction "MGTXTXN2_116_M1") (pintype "output"))
    )
    (net (code "95") (name "unconnected-(U1L-MGTXTXN2_117-PadH1)") (class "Default")
      (node (ref "U1") (pin "H1") (pinfunction "MGTXTXN2_117_H1") (pintype "output"))
    )
    (net (code "96") (name "unconnected-(U1L-MGTXTXN2_118-PadB1)") (class "Default")
      (node (ref "U1") (pin "B1") (pinfunction "MGTXTXN2_118_B1") (pintype "output"))
    )
    (net (code "97") (name "unconnected-(U1L-MGTXTXN3_115-PadT1)") (class "Default")
      (node (ref "U1") (pin "T1") (pinfunction "MGTXTXN3_115_T1") (pintype "output"))
    )
    (net (code "98") (name "unconnected-(U1L-MGTXTXN3_116-PadL3)") (class "Default")
      (node (ref "U1") (pin "L3") (pinfunction "MGTXTXN3_116_L3") (pintype "output"))
    )
    (net (code "99") (name "unconnected-(U1L-MGTXTXN3_117-PadF1)") (class "Default")
      (node (ref "U1") (pin "F1") (pinfunction "MGTXTXN3_117_F1") (pintype "output"))
    )
    (net (code "100") (name "unconnected-(U1L-MGTXTXN3_118-PadA3)") (class "Default")
      (node (ref "U1") (pin "A3") (pinfunction "MGTXTXN3_118_A3") (pintype "output"))
    )
    (net (code "101") (name "unconnected-(U1L-MGTXTXP0_116-PadP2)") (class "Default")
      (node (ref "U1") (pin "P2") (pinfunction "MGTXTXP0_116_P2") (pintype "output"))
    )
    (net (code "102") (name "unconnected-(U1L-MGTXTXP0_117-PadK2)") (class "Default")
      (node (ref "U1") (pin "K2") (pinfunction "MGTXTXP0_117_K2") (pintype "output"))
    )
    (net (code "103") (name "unconnected-(U1L-MGTXTXP0_118-PadD2)") (class "Default")
      (node (ref "U1") (pin "D2") (pinfunction "MGTXTXP0_118_D2") (pintype "output"))
    )
    (net (code "104") (name "unconnected-(U1L-MGTXTXP1_115-PadV2)") (class "Default")
      (node (ref "U1") (pin "V2") (pinfunction "MGTXTXP1_115_V2") (pintype "output"))
    )
    (net (code "105") (name "unconnected-(U1L-MGTXTXP1_116-PadN4)") (class "Default")
      (node (ref "U1") (pin "N4") (pinfunction "MGTXTXP1_116_N4") (pintype "output"))
    )
    (net (code "106") (name "unconnected-(U1L-MGTXTXP1_117-PadJ4)") (class "Default")
      (node (ref "U1") (pin "J4") (pinfunction "MGTXTXP1_117_J4") (pintype "output"))
    )
    (net (code "107") (name "unconnected-(U1L-MGTXTXP1_118-PadC4)") (class "Default")
      (node (ref "U1") (pin "C4") (pinfunction "MGTXTXP1_118_C4") (pintype "output"))
    )
    (net (code "108") (name "unconnected-(U1L-MGTXTXP2_116-PadM2)") (class "Default")
      (node (ref "U1") (pin "M2") (pinfunction "MGTXTXP2_116_M2") (pintype "output"))
    )
    (net (code "109") (name "unconnected-(U1L-MGTXTXP2_117-PadH2)") (class "Default")
      (node (ref "U1") (pin "H2") (pinfunction "MGTXTXP2_117_H2") (pintype "output"))
    )
    (net (code "110") (name "unconnected-(U1L-MGTXTXP2_118-PadB2)") (class "Default")
      (node (ref "U1") (pin "B2") (pinfunction "MGTXTXP2_118_B2") (pintype "output"))
    )
    (net (code "111") (name "unconnected-(U1L-MGTXTXP3_115-PadT2)") (class "Default")
      (node (ref "U1") (pin "T2") (pinfunction "MGTXTXP3_115_T2") (pintype "output"))
    )
    (net (code "112") (name "unconnected-(U1L-MGTXTXP3_116-PadL4)") (class "Default")
      (node (ref "U1") (pin "L4") (pinfunction "MGTXTXP3_116_L4") (pintype "output"))
    )
    (net (code "113") (name "unconnected-(U1L-MGTXTXP3_117-PadF2)") (class "Default")
      (node (ref "U1") (pin "F2") (pinfunction "MGTXTXP3_117_F2") (pintype "output"))
    )
    (net (code "114") (name "unconnected-(U1L-MGTXTXP3_118-PadA4)") (class "Default")
      (node (ref "U1") (pin "A4") (pinfunction "MGTXTXP3_118_A4") (pintype "output"))
    )
    (net (code "115") (name "unconnected-(U3-NC-Pad2)") (class "Default")
      (node (ref "U3") (pin "2") (pinfunction "NC_2") (pintype "passive"))
    )
  )
)
